# 4_multiple_seven_sigment.net
KiCad netlist of a schematic drawn in EAGLE
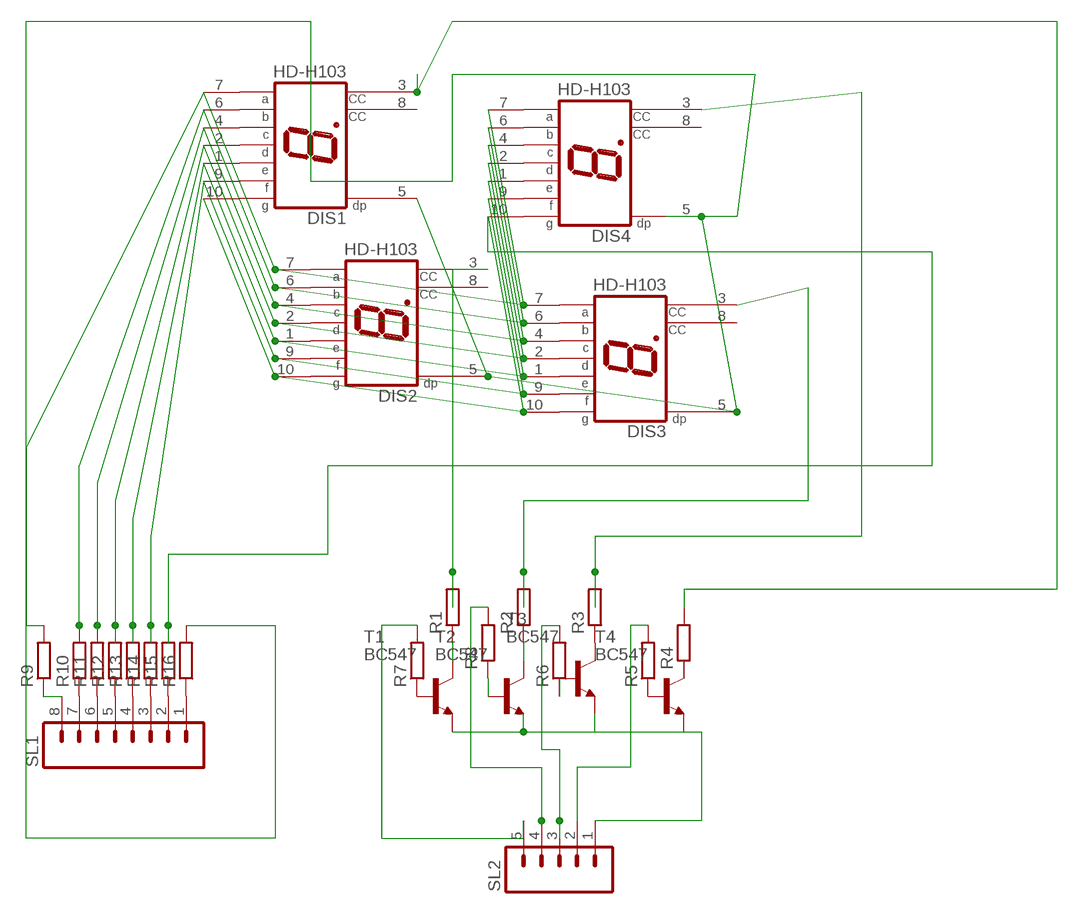
[diagram p0: schematic, sheet 1]

(export (version "E")
  (design (tool "Eeschema 10.0.6"))
  (components
    (comp (ref "DIS1")
      (value "HD-H103")
      (footprint "eagle-import:HDSP-M")
      (libsource (lib "eagle-import") (part "HD-H103"))
    )
    (comp (ref "DIS2")
      (value "HD-H103")
      (footprint "eagle-import:HDSP-M")
      (libsource (lib "eagle-import") (part "HD-H103"))
    )
    (comp (ref "DIS3")
      (value "HD-H103")
      (footprint "eagle-import:HDSP-M")
      (libsource (lib "eagle-import") (part "HD-H103"))
    )
    (comp (ref "DIS4")
      (value "HD-H103")
      (footprint "eagle-import:HDSP-M")
      (libsource (lib "eagle-import") (part "HD-H103"))
    )
    (comp (ref "R1")
      (value "R-EU_0204/7")
      (footprint "eagle-import:0204_7")
      (libsource (lib "eagle-import") (part "R-EU_0204/7"))
    )
    (comp (ref "R2")
      (value "R-EU_0204/7")
      (footprint "eagle-import:0204_7")
      (libsource (lib "eagle-import") (part "R-EU_0204/7"))
    )
    (comp (ref "R3")
      (value "R-EU_0204/7")
      (footprint "eagle-import:0204_7")
      (libsource (lib "eagle-import") (part "R-EU_0204/7"))
    )
    (comp (ref "R4")
      (value "R-EU_0204/7")
      (footprint "eagle-import:0204_7")
      (libsource (lib "eagle-import") (part "R-EU_0204/7"))
    )
    (comp (ref "R5")
      (value "R-EU_0204/7")
      (footprint "eagle-import:0204_7")
      (libsource (lib "eagle-import") (part "R-EU_0204/7"))
    )
    (comp (ref "R6")
      (value "R-EU_0204/7")
      (footprint "eagle-import:0204_7")
      (libsource (lib "eagle-import") (part "R-EU_0204/7"))
    )
    (comp (ref "R7")
      (value "R-EU_0204/7")
      (footprint "eagle-import:0204_7")
      (libsource (lib "eagle-import") (part "R-EU_0204/7"))
    )
    (comp (ref "R8")
      (value "R-EU_0204/7")
      (footprint "eagle-import:0204_7")
      (libsource (lib "eagle-import") (part "R-EU_0204/7"))
    )
    (comp (ref "R9")
      (value "R-EU_0204/7")
      (footprint "eagle-import:0204_7")
      (libsource (lib "eagle-import") (part "R-EU_0204/7"))
    )
    (comp (ref "R10")
      (value "R-EU_0204/7")
      (footprint "eagle-import:0204_7")
      (libsource (lib "eagle-import") (part "R-EU_0204/7"))
    )
    (comp (ref "R11")
      (value "R-EU_0204/7")
      (footprint "eagle-import:0204_7")
      (libsource (lib "eagle-import") (part "R-EU_0204/7"))
    )
    (comp (ref "R12")
      (value "R-EU_0204/7")
      (footprint "eagle-import:0204_7")
      (libsource (lib "eagle-import") (part "R-EU_0204/7"))
    )
    (comp (ref "R13")
      (value "R-EU_0204/7")
      (footprint "eagle-import:0204_7")
      (libsource (lib "eagle-import") (part "R-EU_0204/7"))
    )
    (comp (ref "R14")
      (value "R-EU_0204/7")
      (footprint "eagle-import:0204_7")
      (libsource (lib "eagle-import") (part "R-EU_0204/7"))
    )
    (comp (ref "R15")
      (value "R-EU_0204/7")
      (footprint "eagle-import:0204_7")
      (libsource (lib "eagle-import") (part "R-EU_0204/7"))
    )
    (comp (ref "R16")
      (value "R-EU_0204/7")
      (footprint "eagle-import:0204_7")
      (libsource (lib "eagle-import") (part "R-EU_0204/7"))
    )
    (comp (ref "SL1")
      (value "M08")
      (footprint "eagle-import:08P")
      (libsource (lib "eagle-import") (part "M08"))
    )
    (comp (ref "SL2")
      (value "M05")
      (footprint "eagle-import:05P")
      (libsource (lib "eagle-import") (part "M05"))
    )
    (comp (ref "T1")
      (value "BC547")
      (footprint "eagle-import:TO92")
      (libsource (lib "eagle-import") (part "BC547"))
    )
    (comp (ref "T2")
      (value "BC547")
      (footprint "eagle-import:TO92")
      (libsource (lib "eagle-import") (part "BC547"))
    )
    (comp (ref "T3")
      (value "BC547")
      (footprint "eagle-import:TO92")
      (libsource (lib "eagle-import") (part "BC547"))
    )
    (comp (ref "T4")
      (value "BC547")
      (footprint "eagle-import:TO92")
      (libsource (lib "eagle-import") (part "BC547"))
    )
  )
  (nets
    (net (code "1") (name "Net-(DIS1-A)") (class "Default")
      (node (ref "DIS1") (pin "7") (pinfunction "A_7") (pintype "passive"))
      (node (ref "DIS2") (pin "7") (pinfunction "A_7") (pintype "passive"))
      (node (ref "DIS3") (pin "7") (pinfunction "A_7") (pintype "passive"))
      (node (ref "DIS4") (pin "7") (pinfunction "A_7") (pintype "passive"))
      (node (ref "R9") (pin "2") (pinfunction "2_2") (pintype "passive"))
    )
    (net (code "2") (name "Net-(DIS1-B)") (class "Default")
      (node (ref "DIS1") (pin "6") (pinfunction "B_6") (pintype "passive"))
      (node (ref "DIS2") (pin "6") (pinfunction "B_6") (pintype "passive"))
      (node (ref "DIS3") (pin "6") (pinfunction "B_6") (pintype "passive"))
      (node (ref "DIS4") (pin "6") (pinfunction "B_6") (pintype "passive"))
      (node (ref "R10") (pin "2") (pinfunction "2_2") (pintype "passive"))
    )
    (net (code "3") (name "Net-(DIS1-C)") (class "Default")
      (node (ref "DIS1") (pin "4") (pinfunction "C_4") (pintype "passive"))
      (node (ref "DIS2") (pin "4") (pinfunction "C_4") (pintype "passive"))
      (node (ref "DIS3") (pin "4") (pinfunction "C_4") (pintype "passive"))
      (node (ref "DIS4") (pin "4") (pinfunction "C_4") (pintype "passive"))
      (node (ref "R11") (pin "2") (pinfunction "2_2") (pintype "passive"))
    )
    (net (code "4") (name "Net-(DIS1-CC-Pad3)") (class "Default")
      (node (ref "DIS1") (pin "3") (pinfunction "CC_3") (pintype "passive"))
      (node (ref "R4") (pin "2") (pinfunction "2_2") (pintype "passive"))
    )
    (net (code "5") (name "Net-(DIS1-D)") (class "Default")
      (node (ref "DIS1") (pin "2") (pinfunction "D_2") (pintype "passive"))
      (node (ref "DIS2") (pin "2") (pinfunction "D_2") (pintype "passive"))
      (node (ref "DIS3") (pin "2") (pinfunction "D_2") (pintype "passive"))
      (node (ref "DIS4") (pin "2") (pinfunction "D_2") (pintype "passive"))
      (node (ref "R12") (pin "2") (pinfunction "2_2") (pintype "passive"))
    )
    (net (code "6") (name "Net-(DIS1-DP)") (class "Default")
      (node (ref "DIS1") (pin "5") (pinfunction "DP_5") (pintype "passive"))
      (node (ref "DIS2") (pin "5") (pinfunction "DP_5") (pintype "passive"))
      (node (ref "DIS3") (pin "5") (pinfunction "DP_5") (pintype "passive"))
      (node (ref "DIS4") (pin "5") (pinfunction "DP_5") (pintype "passive"))
      (node (ref "R16") (pin "2") (pinfunction "2_2") (pintype "passive"))
    )
    (net (code "7") (name "Net-(DIS1-E)") (class "Default")
      (node (ref "DIS1") (pin "1") (pinfunction "E_1") (pintype "passive"))
      (node (ref "DIS2") (pin "1") (pinfunction "E_1") (pintype "passive"))
      (node (ref "DIS3") (pin "1") (pinfunction "E_1") (pintype "passive"))
      (node (ref "DIS4") (pin "1") (pinfunction "E_1") (pintype "passive"))
      (node (ref "R13") (pin "2") (pinfunction "2_2") (pintype "passive"))
    )
    (net (code "8") (name "Net-(DIS1-F)") (class "Default")
      (node (ref "DIS1") (pin "9") (pinfunction "F_9") (pintype "passive"))
      (node (ref "DIS2") (pin "9") (pinfunction "F_9") (pintype "passive"))
      (node (ref "DIS3") (pin "9") (pinfunction "F_9") (pintype "passive"))
      (node (ref "DIS4") (pin "9") (pinfunction "F_9") (pintype "passive"))
      (node (ref "R14") (pin "2") (pinfunction "2_2") (pintype "passive"))
    )
    (net (code "9") (name "Net-(DIS1-G)") (class "Default")
      (node (ref "DIS1") (pin "10") (pinfunction "G_10") (pintype "passive"))
      (node (ref "DIS2") (pin "10") (pinfunction "G_10") (pintype "passive"))
      (node (ref "DIS3") (pin "10") (pinfunction "G_10") (pintype "passive"))
      (node (ref "DIS4") (pin "10") (pinfunction "G_10") (pintype "passive"))
      (node (ref "R15") (pin "2") (pinfunction "2_2") (pintype "passive"))
    )
    (net (code "10") (name "Net-(DIS2-CC-Pad3)") (class "Default")
      (node (ref "DIS2") (pin "3") (pinfunction "CC_3") (pintype "passive"))
      (node (ref "R1") (pin "2") (pinfunction "2_2") (pintype "passive"))
    )
    (net (code "11") (name "Net-(DIS3-CC-Pad3)") (class "Default")
      (node (ref "DIS3") (pin "3") (pinfunction "CC_3") (pintype "passive"))
      (node (ref "R2") (pin "2") (pinfunction "2_2") (pintype "passive"))
    )
    (net (code "12") (name "Net-(DIS4-CC-Pad3)") (class "Default")
      (node (ref "DIS4") (pin "3") (pinfunction "CC_3") (pintype "passive"))
      (node (ref "R3") (pin "2") (pinfunction "2_2") (pintype "passive"))
    )
    (net (code "13") (name "Net-(R5-Pad2)") (class "Default")
      (node (ref "R5") (pin "2") (pinfunction "2_2") (pintype "passive"))
      (node (ref "SL2") (pin "2") (pinfunction "2_2") (pintype "passive"))
    )
    (net (code "14") (name "Net-(R6-Pad2)") (class "Default")
      (node (ref "R6") (pin "2") (pinfunction "2_2") (pintype "passive"))
      (node (ref "SL2") (pin "3") (pinfunction "3_3") (pintype "passive"))
    )
    (net (code "15") (name "Net-(R7-Pad2)") (class "Default")
      (node (ref "R7") (pin "2") (pinfunction "2_2") (pintype "passive"))
      (node (ref "SL2") (pin "5") (pinfunction "5_5") (pintype "passive"))
    )
    (net (code "16") (name "Net-(R8-Pad2)") (class "Default")
      (node (ref "R8") (pin "2") (pinfunction "2_2") (pintype "passive"))
      (node (ref "SL2") (pin "4") (pinfunction "4_4") (pintype "passive"))
    )
    (net (code "17") (name "Net-(R9-Pad1)") (class "Default")
      (node (ref "R9") (pin "1") (pinfunction "1_1") (pintype "passive"))
      (node (ref "SL1") (pin "8") (pinfunction "8_8") (pintype "passive"))
    )
    (net (code "18") (name "Net-(R10-Pad1)") (class "Default")
      (node (ref "R10") (pin "1") (pinfunction "1_1") (pintype "passive"))
      (node (ref "SL1") (pin "7") (pinfunction "7_7") (pintype "passive"))
    )
    (net (code "19") (name "Net-(R11-Pad1)") (class "Default")
      (node (ref "R11") (pin "1") (pinfunction "1_1") (pintype "passive"))
      (node (ref "SL1") (pin "6") (pinfunction "6_6") (pintype "passive"))
    )
    (net (code "20") (name "Net-(R12-Pad1)") (class "Default")
      (node (ref "R12") (pin "1") (pinfunction "1_1") (pintype "passive"))
      (node (ref "SL1") (pin "5") (pinfunction "5_5") (pintype "passive"))
    )
    (net (code "21") (name "Net-(R13-Pad1)") (class "Default")
      (node (ref "R13") (pin "1") (pinfunction "1_1") (pintype "passive"))
      (node (ref "SL1") (pin "4") (pinfunction "4_4") (pintype "passive"))
    )
    (net (code "22") (name "Net-(R14-Pad1)") (class "Default")
      (node (ref "R14") (pin "1") (pinfunction "1_1") (pintype "passive"))
      (node (ref "SL1") (pin "3") (pinfunction "3_3") (pintype "passive"))
    )
    (net (code "23") (name "Net-(R15-Pad1)") (class "Default")
      (node (ref "R15") (pin "1") (pinfunction "1_1") (pintype "passive"))
      (node (ref "SL1") (pin "2") (pinfunction "2_2") (pintype "passive"))
    )
    (net (code "24") (name "Net-(R16-Pad1)") (class "Default")
      (node (ref "R16") (pin "1") (pinfunction "1_1") (pintype "passive"))
      (node (ref "SL1") (pin "1") (pinfunction "1_1") (pintype "passive"))
    )
    (net (code "25") (name "Net-(T1-B)") (class "Default")
      (node (ref "R7") (pin "1") (pinfunction "1_1") (pintype "passive"))
      (node (ref "T1") (pin "2") (pinfunction "B_2") (pintype "passive"))
    )
    (net (code "26") (name "Net-(T1-C)") (class "Default")
      (node (ref "R1") (pin "1") (pinfunction "1_1") (pintype "passive"))
      (node (ref "T1") (pin "3") (pinfunction "C_3") (pintype "passive"))
    )
    (net (code "27") (name "Net-(T1-E)") (class "Default")
      (node (ref "SL2") (pin "1") (pinfunction "1_1") (pintype "passive"))
      (node (ref "T1") (pin "1") (pinfunction "E_1") (pintype "passive"))
      (node (ref "T2") (pin "1") (pinfunction "E_1") (pintype "passive"))
      (node (ref "T3") (pin "1") (pinfunction "E_1") (pintype "passive"))
      (node (ref "T4") (pin "1") (pinfunction "E_1") (pintype "passive"))
    )
    (net (code "28") (name "Net-(T2-B)") (class "Default")
      (node (ref "R8") (pin "1") (pinfunction "1_1") (pintype "passive"))
      (node (ref "T2") (pin "2") (pinfunction "B_2") (pintype "passive"))
    )
    (net (code "29") (name "Net-(T2-C)") (class "Default")
      (node (ref "R2") (pin "1") (pinfunction "1_1") (pintype "passive"))
      (node (ref "T2") (pin "3") (pinfunction "C_3") (pintype "passive"))
    )
    (net (code "30") (name "Net-(T3-B)") (class "Default")
      (node (ref "R6") (pin "1") (pinfunction "1_1") (pintype "passive"))
      (node (ref "T3") (pin "2") (pinfunction "B_2") (pintype "passive"))
    )
    (net (code "31") (name "Net-(T3-C)") (class "Default")
      (node (ref "R3") (pin "1") (pinfunction "1_1") (pintype "passive"))
      (node (ref "T3") (pin "3") (pinfunction "C_3") (pintype "passive"))
    )
    (net (code "32") (name "Net-(T4-B)") (class "Default")
      (node (ref "R5") (pin "1") (pinfunction "1_1") (pintype "passive"))
      (node (ref "T4") (pin "2") (pinfunction "B_2") (pintype "passive"))
    )
    (net (code "33") (name "Net-(T4-C)") (class "Default")
      (node (ref "R4") (pin "1") (pinfunction "1_1") (pintype "passive"))
      (node (ref "T4") (pin "3") (pinfunction "C_3") (pintype "passive"))
    )
    (net (code "34") (name "unconnected-(DIS1-CC-Pad8)") (class "Default")
      (node (ref "DIS1") (pin "8") (pinfunction "CC_8") (pintype "passive"))
    )
    (net (code "35") (name "unconnected-(DIS2-CC-Pad8)") (class "Default")
      (node (ref "DIS2") (pin "8") (pinfunction "CC_8") (pintype "passive"))
    )
    (net (code "36") (name "unconnected-(DIS3-CC-Pad8)") (class "Default")
      (node (ref "DIS3") (pin "8") (pinfunction "CC_8") (pintype "passive"))
    )
    (net (code "37") (name "unconnected-(DIS4-CC-Pad8)") (class "Default")
      (node (ref "DIS4") (pin "8") (pinfunction "CC_8") (pintype "passive"))
    )
  )
)
